# untitled.net
KiCad netlist of a schematic drawn in EAGLE
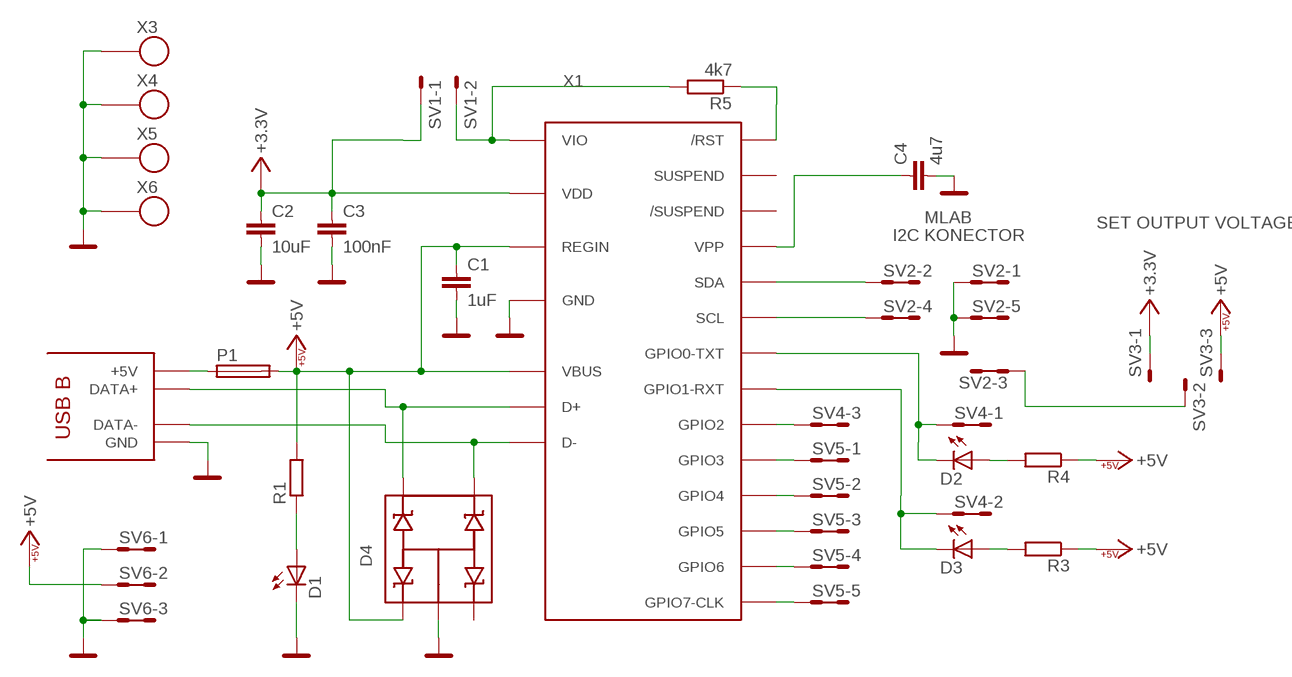
[diagram p0: schematic, sheet 1]

(export (version "E")
  (design (tool "Eeschema 10.0.6"))
  (components
    (comp (ref "C1")
      (value "1uF")
      (footprint "eagle-import:C0805")
      (libsource (lib "eagle-import") (part "C0805"))
    )
    (comp (ref "C2")
      (value "10uF")
      (footprint "eagle-import:C0805")
      (libsource (lib "eagle-import") (part "C0805"))
    )
    (comp (ref "C3")
      (value "100nF")
      (footprint "eagle-import:C0805")
      (libsource (lib "eagle-import") (part "C0805"))
    )
    (comp (ref "C4")
      (value "4u7")
      (footprint "eagle-import:C0805")
      (libsource (lib "eagle-import") (part "C0805"))
    )
    (comp (ref "D1")
      (value "LED1206_2")
      (footprint "eagle-import:1206_2")
      (libsource (lib "eagle-import") (part "LED1206_2"))
    )
    (comp (ref "D2")
      (value "LED1206_2")
      (footprint "eagle-import:1206_2")
      (libsource (lib "eagle-import") (part "LED1206_2"))
    )
    (comp (ref "D3")
      (value "LED1206_2")
      (footprint "eagle-import:1206_2")
      (libsource (lib "eagle-import") (part "LED1206_2"))
    )
    (comp (ref "D4")
      (value "CP2112")
      (footprint "eagle-import:SOT553")
      (libsource (lib "eagle-import") (part "CP2112"))
    )
    (comp (ref "P1")
      (value "POJISTKA_1812")
      (footprint "eagle-import:1812")
      (libsource (lib "eagle-import") (part "POJISTKA_1812"))
    )
    (comp (ref "R1")
      (value "R0805")
      (footprint "eagle-import:0805")
      (libsource (lib "eagle-import") (part "R0805"))
    )
    (comp (ref "R3")
      (value "R0805")
      (footprint "eagle-import:0805")
      (libsource (lib "eagle-import") (part "R0805"))
    )
    (comp (ref "R4")
      (value "R0805")
      (footprint "eagle-import:0805")
      (libsource (lib "eagle-import") (part "R0805"))
    )
    (comp (ref "R5")
      (value "4k7")
      (footprint "eagle-import:0805")
      (libsource (lib "eagle-import") (part "R0805"))
    )
    (comp (ref "SV1")
      (value "MA02-1")
      (footprint "eagle-import:MA02-1")
      (libsource (lib "eagle-import") (part "MA02-1"))
    )
    (comp (ref "SV2")
      (value "MA05-2")
      (footprint "eagle-import:MA05-2")
      (libsource (lib "eagle-import") (part "MA05-2"))
    )
    (comp (ref "SV3")
      (value "MA03-1")
      (footprint "eagle-import:MA03-1")
      (libsource (lib "eagle-import") (part "MA03-1"))
    )
    (comp (ref "SV4")
      (value "MA03-2")
      (footprint "eagle-import:MA03-2")
      (libsource (lib "eagle-import") (part "MA03-2"))
    )
    (comp (ref "SV5")
      (value "MA05-2")
      (footprint "eagle-import:MA05-2")
      (libsource (lib "eagle-import") (part "MA05-2"))
    )
    (comp (ref "SV6")
      (value "MA03-2")
      (footprint "eagle-import:MA03-2")
      (libsource (lib "eagle-import") (part "MA03-2"))
    )
    (comp (ref "X1")
      (value "CP2112")
      (footprint "eagle-import:QFN-24")
      (libsource (lib "eagle-import") (part "moje_io_CP2112"))
    )
    (comp (ref "X2")
      (value "USB_B")
      (footprint "eagle-import:USB_B")
      (libsource (lib "eagle-import") (part "USB_B"))
    )
    (comp (ref "X3")
      (value "SROUB3M")
      (footprint "eagle-import:SROUB3M")
      (libsource (lib "eagle-import") (part "SROUB3M"))
    )
    (comp (ref "X4")
      (value "SROUB3M")
      (footprint "eagle-import:SROUB3M")
      (libsource (lib "eagle-import") (part "SROUB3M"))
    )
    (comp (ref "X5")
      (value "SROUB3M")
      (footprint "eagle-import:SROUB3M")
      (libsource (lib "eagle-import") (part "SROUB3M"))
    )
    (comp (ref "X6")
      (value "SROUB3M")
      (footprint "eagle-import:SROUB3M")
      (libsource (lib "eagle-import") (part "SROUB3M"))
    )
  )
  (nets
    (net (code "1") (name "+3.3V") (class "Default")
      (node (ref "C2") (pin "1") (pinfunction "1_1") (pintype "passive"))
      (node (ref "C3") (pin "1") (pinfunction "1_1") (pintype "passive"))
      (node (ref "SV1") (pin "1") (pinfunction "P$1_1") (pintype "passive"))
      (node (ref "SV3") (pin "1") (pinfunction "P$1_1") (pintype "passive"))
      (node (ref "X1") (pin "P$6") (pinfunction "VDD_P$6") (pintype "bidirectional"))
    )
    (net (code "2") (name "+5V") (class "Default")
      (node (ref "C1") (pin "1") (pinfunction "1_1") (pintype "passive"))
      (node (ref "D4") (pin "1") (pinfunction "P$1_1") (pintype "passive"))
      (node (ref "P1") (pin "2") (pinfunction "2_2") (pintype "passive"))
      (node (ref "R1") (pin "2") (pinfunction "2_2") (pintype "passive"))
      (node (ref "R3") (pin "1") (pinfunction "1_1") (pintype "passive"))
      (node (ref "R4") (pin "1") (pinfunction "1_1") (pintype "passive"))
      (node (ref "SV3") (pin "3") (pinfunction "P$1_3") (pintype "passive"))
      (node (ref "SV6") (pin "3") (pinfunction "K_3") (pintype "passive"))
      (node (ref "SV6") (pin "4") (pinfunction "K_4") (pintype "passive"))
      (node (ref "X1") (pin "P$7") (pinfunction "REGIN_P$7") (pintype "bidirectional"))
      (node (ref "X1") (pin "P$8") (pinfunction "VBUS_P$8") (pintype "bidirectional"))
    )
    (net (code "3") (name "GND") (class "Default")
      (node (ref "C1") (pin "2") (pinfunction "2_2") (pintype "passive"))
      (node (ref "C2") (pin "2") (pinfunction "2_2") (pintype "passive"))
      (node (ref "C3") (pin "2") (pinfunction "2_2") (pintype "passive"))
      (node (ref "C4") (pin "2") (pinfunction "2_2") (pintype "passive"))
      (node (ref "D1") (pin "K") (pinfunction "C_K") (pintype "passive"))
      (node (ref "D4") (pin "2") (pinfunction "P$2_2") (pintype "passive"))
      (node (ref "SV2") (pin "1") (pinfunction "K_1") (pintype "passive"))
      (node (ref "SV2") (pin "10") (pinfunction "K_10") (pintype "passive"))
      (node (ref "SV2") (pin "2") (pinfunction "K_2") (pintype "passive"))
      (node (ref "SV2") (pin "9") (pinfunction "K_9") (pintype "passive"))
      (node (ref "SV6") (pin "1") (pinfunction "K_1") (pintype "passive"))
      (node (ref "SV6") (pin "2") (pinfunction "K_2") (pintype "passive"))
      (node (ref "SV6") (pin "5") (pinfunction "K_5") (pintype "passive"))
      (node (ref "SV6") (pin "6") (pinfunction "K_6") (pintype "passive"))
      (node (ref "X1") (pin "P$2") (pinfunction "GND_P$2") (pintype "bidirectional"))
      (node (ref "X1") (pin "P$25") (pinfunction "GND_P$25") (pintype "bidirectional"))
      (node (ref "X2") (pin "4") (pinfunction "GND_4") (pintype "bidirectional"))
      (node (ref "X2") (pin "GND") (pinfunction "GND_GND") (pintype "bidirectional"))
      (node (ref "X2") (pin "GND2") (pinfunction "GND_GND2") (pintype "bidirectional"))
      (node (ref "X3") (pin "P$1") (pinfunction "P$1_P$1") (pintype "bidirectional"))
      (node (ref "X4") (pin "P$1") (pinfunction "P$1_P$1") (pintype "bidirectional"))
      (node (ref "X5") (pin "P$1") (pinfunction "P$1_P$1") (pintype "bidirectional"))
      (node (ref "X6") (pin "P$1") (pinfunction "P$1_P$1") (pintype "bidirectional"))
    )
    (net (code "4") (name "Net-(D1-PadA)") (class "Default")
      (node (ref "D1") (pin "A") (pinfunction "A_A") (pintype "passive"))
      (node (ref "R1") (pin "1") (pinfunction "1_1") (pintype "passive"))
    )
    (net (code "5") (name "Net-(D2-C)") (class "Default")
      (node (ref "D2") (pin "K") (pinfunction "C_K") (pintype "passive"))
      (node (ref "SV4") (pin "1") (pinfunction "K_1") (pintype "passive"))
      (node (ref "SV4") (pin "2") (pinfunction "K_2") (pintype "passive"))
      (node (ref "X1") (pin "P$23") (pinfunction "GPIO0-TXT_P$23") (pintype "bidirectional"))
    )
    (net (code "6") (name "Net-(D2-PadA)") (class "Default")
      (node (ref "D2") (pin "A") (pinfunction "A_A") (pintype "passive"))
      (node (ref "R4") (pin "2") (pinfunction "2_2") (pintype "passive"))
    )
    (net (code "7") (name "Net-(D3-C)") (class "Default")
      (node (ref "D3") (pin "K") (pinfunction "C_K") (pintype "passive"))
      (node (ref "SV4") (pin "3") (pinfunction "K_3") (pintype "passive"))
      (node (ref "SV4") (pin "4") (pinfunction "K_4") (pintype "passive"))
      (node (ref "X1") (pin "P$22") (pinfunction "GPIO1-RXT_P$22") (pintype "bidirectional"))
    )
    (net (code "8") (name "Net-(D3-PadA)") (class "Default")
      (node (ref "D3") (pin "A") (pinfunction "A_A") (pintype "passive"))
      (node (ref "R3") (pin "2") (pinfunction "2_2") (pintype "passive"))
    )
    (net (code "9") (name "Net-(D4-P$4)") (class "Default")
      (node (ref "D4") (pin "4") (pinfunction "P$4_4") (pintype "passive"))
      (node (ref "X1") (pin "P$4") (pinfunction "D-_P$4") (pintype "bidirectional"))
      (node (ref "X2") (pin "2") (pinfunction "DATA-_2") (pintype "bidirectional"))
    )
    (net (code "10") (name "Net-(D4-P$5)") (class "Default")
      (node (ref "D4") (pin "5") (pinfunction "P$5_5") (pintype "passive"))
      (node (ref "X1") (pin "P$3") (pinfunction "D+_P$3") (pintype "bidirectional"))
      (node (ref "X2") (pin "3") (pinfunction "DATA+_3") (pintype "bidirectional"))
    )
    (net (code "11") (name "Net-(SV1B-P$1)") (class "Default")
      (node (ref "R5") (pin "2") (pinfunction "2_2") (pintype "passive"))
      (node (ref "SV1") (pin "2") (pinfunction "P$1_2") (pintype "passive"))
      (node (ref "X1") (pin "P$5") (pinfunction "VIO_P$5") (pintype "bidirectional"))
    )
    (net (code "12") (name "Net-(SV3B-P$1)") (class "Default")
      (node (ref "SV2") (pin "5") (pinfunction "K_5") (pintype "passive"))
      (node (ref "SV2") (pin "6") (pinfunction "K_6") (pintype "passive"))
      (node (ref "SV3") (pin "2") (pinfunction "P$1_2") (pintype "passive"))
    )
    (net (code "13") (name "Net-(X1-GPIO2)") (class "Default")
      (node (ref "SV4") (pin "5") (pinfunction "K_5") (pintype "passive"))
      (node (ref "SV4") (pin "6") (pinfunction "K_6") (pintype "passive"))
      (node (ref "X1") (pin "P$21") (pinfunction "GPIO2_P$21") (pintype "bidirectional"))
    )
    (net (code "14") (name "Net-(X1-GPIO3)") (class "Default")
      (node (ref "SV5") (pin "1") (pinfunction "K_1") (pintype "passive"))
      (node (ref "SV5") (pin "2") (pinfunction "K_2") (pintype "passive"))
      (node (ref "X1") (pin "P$20") (pinfunction "GPIO3_P$20") (pintype "bidirectional"))
    )
    (net (code "15") (name "Net-(X1-GPIO4)") (class "Default")
      (node (ref "SV5") (pin "3") (pinfunction "K_3") (pintype "passive"))
      (node (ref "SV5") (pin "4") (pinfunction "K_4") (pintype "passive"))
      (node (ref "X1") (pin "P$15") (pinfunction "GPIO4_P$15") (pintype "bidirectional"))
    )
    (net (code "16") (name "Net-(X1-GPIO5)") (class "Default")
      (node (ref "SV5") (pin "5") (pinfunction "K_5") (pintype "passive"))
      (node (ref "SV5") (pin "6") (pinfunction "K_6") (pintype "passive"))
      (node (ref "X1") (pin "P$14") (pinfunction "GPIO5_P$14") (pintype "bidirectional"))
    )
    (net (code "17") (name "Net-(X1-GPIO6)") (class "Default")
      (node (ref "SV5") (pin "7") (pinfunction "K_7") (pintype "passive"))
      (node (ref "SV5") (pin "8") (pinfunction "K_8") (pintype "passive"))
      (node (ref "X1") (pin "P$13") (pinfunction "GPIO6_P$13") (pintype "bidirectional"))
    )
    (net (code "18") (name "Net-(X1-GPIO7-CLK)") (class "Default")
      (node (ref "SV5") (pin "10") (pinfunction "K_10") (pintype "passive"))
      (node (ref "SV5") (pin "9") (pinfunction "K_9") (pintype "passive"))
      (node (ref "X1") (pin "P$12") (pinfunction "GPIO7-CLK_P$12") (pintype "bidirectional"))
    )
    (net (code "19") (name "Net-(X1-SCL)") (class "Default")
      (node (ref "SV2") (pin "7") (pinfunction "K_7") (pintype "passive"))
      (node (ref "SV2") (pin "8") (pinfunction "K_8") (pintype "passive"))
      (node (ref "X1") (pin "P$24") (pinfunction "SCL_P$24") (pintype "bidirectional"))
    )
    (net (code "20") (name "Net-(X1-SDA)") (class "Default")
      (node (ref "SV2") (pin "3") (pinfunction "K_3") (pintype "passive"))
      (node (ref "SV2") (pin "4") (pinfunction "K_4") (pintype "passive"))
      (node (ref "X1") (pin "P$1") (pinfunction "SDA_P$1") (pintype "bidirectional"))
    )
    (net (code "21") (name "Net-(X1-VPP)") (class "Default")
      (node (ref "C4") (pin "1") (pinfunction "1_1") (pintype "passive"))
      (node (ref "X1") (pin "P$16") (pinfunction "VPP_P$16") (pintype "bidirectional"))
    )
    (net (code "22") (name "Net-(X1-{slash}RST)") (class "Default")
      (node (ref "R5") (pin "1") (pinfunction "1_1") (pintype "passive"))
      (node (ref "X1") (pin "P$9") (pinfunction "/RST_P$9") (pintype "bidirectional"))
    )
    (net (code "23") (name "Net-(X2-+5V)") (class "Default")
      (node (ref "P1") (pin "1") (pinfunction "1_1") (pintype "passive"))
      (node (ref "X2") (pin "1") (pinfunction "+5V_1") (pintype "bidirectional"))
    )
    (net (code "24") (name "unconnected-(D4-P$3-Pad3)") (class "Default")
      (node (ref "D4") (pin "3") (pinfunction "P$3_3") (pintype "passive"))
    )
    (net (code "25") (name "unconnected-(X1-SUSPEND-PadP$11)") (class "Default")
      (node (ref "X1") (pin "P$11") (pinfunction "SUSPEND_P$11") (pintype "bidirectional"))
    )
    (net (code "26") (name "unconnected-(X1-{slash}SUSPEND-PadP$17)") (class "Default")
      (node (ref "X1") (pin "P$17") (pinfunction "/SUSPEND_P$17") (pintype "bidirectional"))
    )
  )
)
